# SHDN-BSPD-S11-V00-Buzzer.net
KiCad netlist of a schematic drawn in Altium Designer
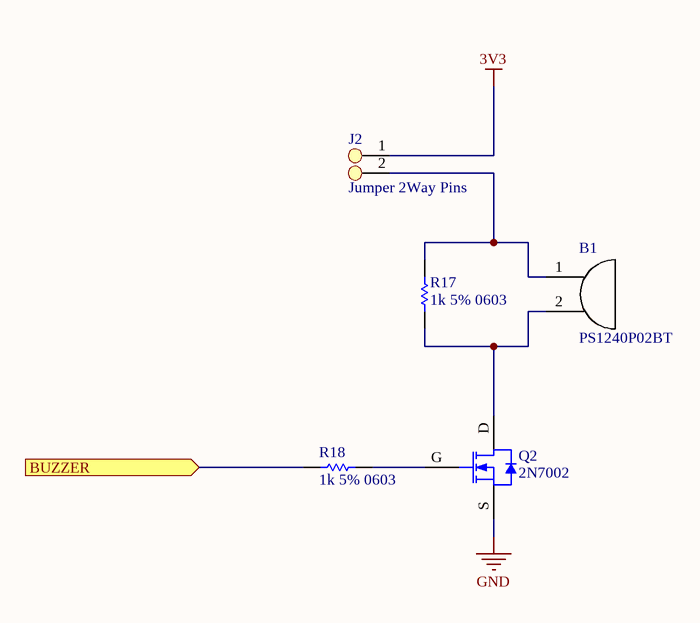
[diagram p0: SHDN-BSPD-S11-V00-Buzzer.SchDoc]

(export (version "E")
  (design (tool "Eeschema 10.0.6"))
  (components
    (comp (ref "B1")
      (value "PS1240P02BT")
      (footprint "PS1240P02BT")
      (description "Buzzers Transducer, Externally Driven Piezo 3V 4kHz 60dB @ 3V, 10cm Through Hole PC Pins")
      (libsource (lib "QUTMS_BuzzerLibrary") (part "PS1240P02BT"))
    )
    (comp (ref "J2")
      (value "Jumper 2Way Pins")
      (footprint "Jumper_2Way_Pin")
      (description "Jumper 2Way Side Pins")
      (libsource (lib "QUTMS_JumperLibrary") (part "Jumper 2Way Side Pins"))
    )
    (comp (ref "Q2")
      (value "2N7002")
      (footprint "SOT23-3")
      (libsource (lib "QUTMS_MOSFETLibrary") (part "2N7002"))
    )
    (comp (ref "R17")
      (value "1k 5% 0603")
      (footprint "Res_ThinFilm_0603")
      (description "Resistor, SMD, 1k, 0.1W, 5%, 0603")
      (libsource (lib "StandardResistors") (part "1k 5% 0603"))
    )
    (comp (ref "R18")
      (value "1k 5% 0603")
      (footprint "Res_ThinFilm_0603")
      (description "Resistor, SMD, 1k, 0.1W, 5%, 0603")
      (libsource (lib "StandardResistors") (part "1k 5% 0603"))
    )
  )
  (nets
    (net (code "1") (name "/BUZZER") (class "Default")
      (node (ref "R18") (pin "2") (pinfunction "2_2") (pintype "passive"))
    )
    (net (code "2") (name "3V3") (class "Default")
      (node (ref "J2") (pin "1") (pinfunction "1_1") (pintype "passive"))
    )
    (net (code "3") (name "GND") (class "Default")
      (node (ref "Q2") (pin "S") (pinfunction "S_S") (pintype "passive"))
    )
    (net (code "4") (name "Net-(B1-Pad1)") (class "Default")
      (node (ref "B1") (pin "1") (pinfunction "1_1") (pintype "passive"))
      (node (ref "J2") (pin "2") (pinfunction "2_2") (pintype "passive"))
      (node (ref "R17") (pin "2") (pinfunction "2_2") (pintype "passive"))
    )
    (net (code "5") (name "Net-(B1-Pad2)") (class "Default")
      (node (ref "B1") (pin "2") (pinfunction "2_2") (pintype "passive"))
      (node (ref "Q2") (pin "D") (pinfunction "D_D") (pintype "passive"))
      (node (ref "R17") (pin "1") (pinfunction "1_1") (pintype "passive"))
    )
    (net (code "6") (name "Net-(Q2-PadG)") (class "Default")
      (node (ref "Q2") (pin "G") (pinfunction "G_G") (pintype "passive"))
      (node (ref "R18") (pin "1") (pinfunction "1_1") (pintype "passive"))
    )
  )
)
